# ftdi.net
KiCad netlist of a schematic drawn in EAGLE
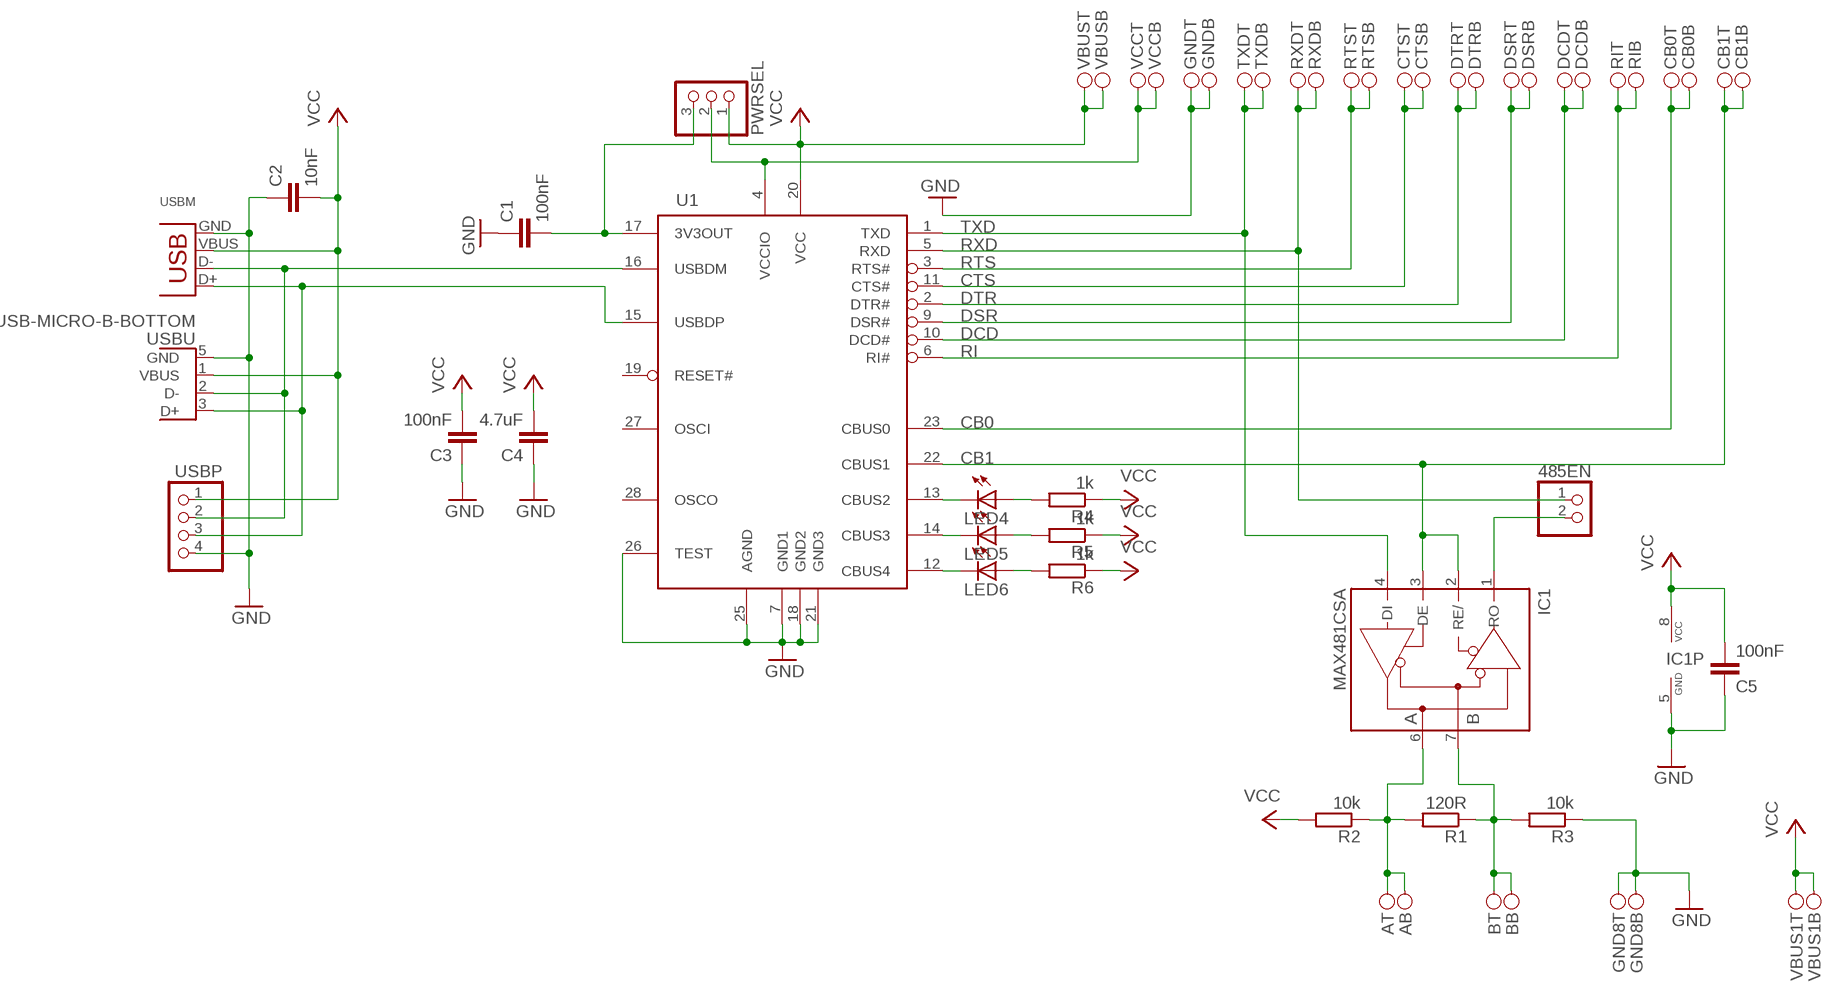
[diagram p0: schematic, sheet 1]

(export (version "E")
  (design (tool "Eeschema 10.0.6"))
  (components
    (comp (ref "485EN")
      (value "PINHD-1X2/90")
      (footprint "eagle-import:1X02_90")
      (libsource (lib "eagle-import") (part "PINHD-1X2/90"))
    )
    (comp (ref "A")
      (value "PINH2X01")
      (footprint "eagle-import:PINH2X01SMD")
      (libsource (lib "eagle-import") (part "PINH2X01"))
    )
    (comp (ref "B")
      (value "PINH2X01")
      (footprint "eagle-import:PINH2X01SMD")
      (libsource (lib "eagle-import") (part "PINH2X01"))
    )
    (comp (ref "C1")
      (value "100nF")
      (footprint "eagle-import:C0402")
      (libsource (lib "eagle-import") (part "C-EUC0402"))
    )
    (comp (ref "C2")
      (value "10nF")
      (footprint "eagle-import:C0603")
      (libsource (lib "eagle-import") (part "C-EUC0603"))
    )
    (comp (ref "C3")
      (value "100nF")
      (footprint "eagle-import:C0402")
      (libsource (lib "eagle-import") (part "C-EUC0402"))
    )
    (comp (ref "C4")
      (value "4.7uF")
      (footprint "eagle-import:C0805K")
      (libsource (lib "eagle-import") (part "C-EUC0805K"))
    )
    (comp (ref "C5")
      (value "100nF")
      (footprint "eagle-import:C0402")
      (libsource (lib "eagle-import") (part "C-EUC0402"))
    )
    (comp (ref "CB0")
      (value "PINH2X01")
      (footprint "eagle-import:PINH2X01SMD")
      (libsource (lib "eagle-import") (part "PINH2X01"))
    )
    (comp (ref "CB1")
      (value "PINH2X01")
      (footprint "eagle-import:PINH2X01SMD")
      (libsource (lib "eagle-import") (part "PINH2X01"))
    )
    (comp (ref "CTS")
      (value "PINH2X01")
      (footprint "eagle-import:PINH2X01SMD")
      (libsource (lib "eagle-import") (part "PINH2X01"))
    )
    (comp (ref "DCD")
      (value "PINH2X01")
      (footprint "eagle-import:PINH2X01SMD")
      (libsource (lib "eagle-import") (part "PINH2X01"))
    )
    (comp (ref "DSR")
      (value "PINH2X01")
      (footprint "eagle-import:PINH2X01SMD")
      (libsource (lib "eagle-import") (part "PINH2X01"))
    )
    (comp (ref "DTR")
      (value "PINH2X01")
      (footprint "eagle-import:PINH2X01SMD")
      (libsource (lib "eagle-import") (part "PINH2X01"))
    )
    (comp (ref "GND")
      (value "PINH2X01")
      (footprint "eagle-import:PINH2X01SMD")
      (libsource (lib "eagle-import") (part "PINH2X01"))
    )
    (comp (ref "GND8")
      (value "PINH2X01")
      (footprint "eagle-import:PINH2X01SMD")
      (libsource (lib "eagle-import") (part "PINH2X01"))
    )
    (comp (ref "IC1")
      (value "MAX481CSA")
      (footprint "eagle-import:SO08")
      (fields (field (name "MF") "MAXIM"))
      (libsource (lib "eagle-import") (part "MAX481CSA"))
    )
    (comp (ref "LED4")
      (value "LEDCHIPLED_0603")
      (footprint "eagle-import:CHIPLED_0603")
      (libsource (lib "eagle-import") (part "LEDCHIPLED_0603"))
    )
    (comp (ref "LED5")
      (value "LEDCHIPLED_0603")
      (footprint "eagle-import:CHIPLED_0603")
      (libsource (lib "eagle-import") (part "LEDCHIPLED_0603"))
    )
    (comp (ref "LED6")
      (value "LEDCHIPLED_0603")
      (footprint "eagle-import:CHIPLED_0603")
      (libsource (lib "eagle-import") (part "LEDCHIPLED_0603"))
    )
    (comp (ref "PWRSEL")
      (value "PINHD-1X3/90")
      (footprint "eagle-import:1X03_90")
      (libsource (lib "eagle-import") (part "PINHD-1X3/90"))
    )
    (comp (ref "R1")
      (value "120R")
      (footprint "eagle-import:R0603")
      (libsource (lib "eagle-import") (part "R-EU_R0603"))
    )
    (comp (ref "R2")
      (value "10k")
      (footprint "eagle-import:R0603")
      (libsource (lib "eagle-import") (part "R-EU_R0603"))
    )
    (comp (ref "R3")
      (value "10k")
      (footprint "eagle-import:R0603")
      (libsource (lib "eagle-import") (part "R-EU_R0603"))
    )
    (comp (ref "R4")
      (value "1k")
      (footprint "eagle-import:R0603")
      (libsource (lib "eagle-import") (part "R-EU_R0603"))
    )
    (comp (ref "R5")
      (value "1k")
      (footprint "eagle-import:R0603")
      (libsource (lib "eagle-import") (part "R-EU_R0603"))
    )
    (comp (ref "R6")
      (value "1k")
      (footprint "eagle-import:R0603")
      (libsource (lib "eagle-import") (part "R-EU_R0603"))
    )
    (comp (ref "RI")
      (value "PINH2X01")
      (footprint "eagle-import:PINH2X01SMD")
      (libsource (lib "eagle-import") (part "PINH2X01"))
    )
    (comp (ref "RTS")
      (value "PINH2X01")
      (footprint "eagle-import:PINH2X01SMD")
      (libsource (lib "eagle-import") (part "PINH2X01"))
    )
    (comp (ref "RXD")
      (value "PINH2X01")
      (footprint "eagle-import:PINH2X01SMD")
      (libsource (lib "eagle-import") (part "PINH2X01"))
    )
    (comp (ref "TXD")
      (value "PINH2X01")
      (footprint "eagle-import:PINH2X01SMD")
      (libsource (lib "eagle-import") (part "PINH2X01"))
    )
    (comp (ref "U1")
      (value "FT232RL")
      (footprint "eagle-import:SSOP28DB")
      (libsource (lib "eagle-import") (part "FT232RL"))
    )
    (comp (ref "USBM")
      (value "USB-MB-S")
      (footprint "eagle-import:USB-MB-S")
      (libsource (lib "eagle-import") (part "USB-MB-S"))
    )
    (comp (ref "USBP")
      (value "PINHD-1X4")
      (footprint "eagle-import:1X04")
      (libsource (lib "eagle-import") (part "PINHD-1X4"))
    )
    (comp (ref "USBU")
      (value "USB-MICRO-B-BOTTOM")
      (footprint "eagle-import:USB-MICRO-B-BOTTOM-MOLEX")
      (libsource (lib "eagle-import") (part "USB-MICRO-B-BOTTOM"))
    )
    (comp (ref "VBUS")
      (value "PINH2X01")
      (footprint "eagle-import:PINH2X01SMD")
      (libsource (lib "eagle-import") (part "PINH2X01"))
    )
    (comp (ref "VBUS1")
      (value "PINH2X01")
      (footprint "eagle-import:PINH2X01SMD")
      (libsource (lib "eagle-import") (part "PINH2X01"))
    )
    (comp (ref "VCC")
      (value "PINH2X01")
      (footprint "eagle-import:PINH2X01SMD")
      (libsource (lib "eagle-import") (part "PINH2X01"))
    )
  )
  (nets
    (net (code "1") (name "/CB0") (class "Default")
      (node (ref "CB0") (pin "1") (pinfunction "1_1") (pintype "passive"))
      (node (ref "CB0") (pin "2") (pinfunction "1_2") (pintype "passive"))
      (node (ref "U1") (pin "23") (pinfunction "CBUS0_23") (pintype "bidirectional"))
    )
    (net (code "2") (name "/CB1") (class "Default")
      (node (ref "CB1") (pin "1") (pinfunction "1_1") (pintype "passive"))
      (node (ref "CB1") (pin "2") (pinfunction "1_2") (pintype "passive"))
      (node (ref "IC1") (pin "2") (pinfunction "RE/_2") (pintype "input"))
      (node (ref "IC1") (pin "3") (pinfunction "DE_3") (pintype "input"))
      (node (ref "U1") (pin "22") (pinfunction "CBUS1_22") (pintype "bidirectional"))
    )
    (net (code "3") (name "/CTS") (class "Default")
      (node (ref "CTS") (pin "1") (pinfunction "1_1") (pintype "passive"))
      (node (ref "CTS") (pin "2") (pinfunction "1_2") (pintype "passive"))
      (node (ref "U1") (pin "11") (pinfunction "CTS#_11") (pintype "input"))
    )
    (net (code "4") (name "/DCD") (class "Default")
      (node (ref "DCD") (pin "1") (pinfunction "1_1") (pintype "passive"))
      (node (ref "DCD") (pin "2") (pinfunction "1_2") (pintype "passive"))
      (node (ref "U1") (pin "10") (pinfunction "DCD#_10") (pintype "input"))
    )
    (net (code "5") (name "/DSR") (class "Default")
      (node (ref "DSR") (pin "1") (pinfunction "1_1") (pintype "passive"))
      (node (ref "DSR") (pin "2") (pinfunction "1_2") (pintype "passive"))
      (node (ref "U1") (pin "9") (pinfunction "DSR#_9") (pintype "input"))
    )
    (net (code "6") (name "/DTR") (class "Default")
      (node (ref "DTR") (pin "1") (pinfunction "1_1") (pintype "passive"))
      (node (ref "DTR") (pin "2") (pinfunction "1_2") (pintype "passive"))
      (node (ref "U1") (pin "2") (pinfunction "DTR#_2") (pintype "output"))
    )
    (net (code "7") (name "/RI") (class "Default")
      (node (ref "RI") (pin "1") (pinfunction "1_1") (pintype "passive"))
      (node (ref "RI") (pin "2") (pinfunction "1_2") (pintype "passive"))
      (node (ref "U1") (pin "6") (pinfunction "RI#_6") (pintype "input"))
    )
    (net (code "8") (name "/RTS") (class "Default")
      (node (ref "RTS") (pin "1") (pinfunction "1_1") (pintype "passive"))
      (node (ref "RTS") (pin "2") (pinfunction "1_2") (pintype "passive"))
      (node (ref "U1") (pin "3") (pinfunction "RTS#_3") (pintype "output"))
    )
    (net (code "9") (name "/RXD") (class "Default")
      (node (ref "485EN") (pin "1") (pinfunction "1_1") (pintype "passive"))
      (node (ref "RXD") (pin "1") (pinfunction "1_1") (pintype "passive"))
      (node (ref "RXD") (pin "2") (pinfunction "1_2") (pintype "passive"))
      (node (ref "U1") (pin "5") (pinfunction "RXD_5") (pintype "input"))
    )
    (net (code "10") (name "/TXD") (class "Default")
      (node (ref "IC1") (pin "4") (pinfunction "DI_4") (pintype "input"))
      (node (ref "TXD") (pin "1") (pinfunction "1_1") (pintype "passive"))
      (node (ref "TXD") (pin "2") (pinfunction "1_2") (pintype "passive"))
      (node (ref "U1") (pin "1") (pinfunction "TXD_1") (pintype "output"))
    )
    (net (code "11") (name "GND") (class "Default")
      (node (ref "C1") (pin "1") (pinfunction "1_1") (pintype "passive"))
      (node (ref "C2") (pin "1") (pinfunction "1_1") (pintype "passive"))
      (node (ref "C3") (pin "1") (pinfunction "1_1") (pintype "passive"))
      (node (ref "C4") (pin "1") (pinfunction "1_1") (pintype "passive"))
      (node (ref "C5") (pin "1") (pinfunction "1_1") (pintype "passive"))
      (node (ref "GND") (pin "1") (pinfunction "1_1") (pintype "passive"))
      (node (ref "GND") (pin "2") (pinfunction "1_2") (pintype "passive"))
      (node (ref "GND8") (pin "1") (pinfunction "1_1") (pintype "passive"))
      (node (ref "GND8") (pin "2") (pinfunction "1_2") (pintype "passive"))
      (node (ref "IC1") (pin "5") (pinfunction "GND_5") (pintype "power_in"))
      (node (ref "R3") (pin "1") (pinfunction "1_1") (pintype "passive"))
      (node (ref "U1") (pin "18") (pinfunction "GND2_18") (pintype "power_in"))
      (node (ref "U1") (pin "21") (pinfunction "GND3_21") (pintype "power_in"))
      (node (ref "U1") (pin "25") (pinfunction "AGND_25") (pintype "power_in"))
      (node (ref "U1") (pin "26") (pinfunction "TEST_26") (pintype "input"))
      (node (ref "U1") (pin "7") (pinfunction "GND1_7") (pintype "power_in"))
      (node (ref "USBM") (pin "GND") (pinfunction "GND_GND") (pintype "bidirectional"))
      (node (ref "USBP") (pin "4") (pinfunction "4_4") (pintype "passive"))
      (node (ref "USBU") (pin "5") (pinfunction "GND_5") (pintype "passive"))
    )
    (net (code "12") (name "Net-(AA-1)") (class "Default")
      (node (ref "A") (pin "1") (pinfunction "1_1") (pintype "passive"))
      (node (ref "A") (pin "2") (pinfunction "1_2") (pintype "passive"))
      (node (ref "IC1") (pin "6") (pinfunction "A_6") (pintype "passive"))
      (node (ref "R1") (pin "2") (pinfunction "2_2") (pintype "passive"))
      (node (ref "R2") (pin "1") (pinfunction "1_1") (pintype "passive"))
    )
    (net (code "13") (name "Net-(BA-1)") (class "Default")
      (node (ref "B") (pin "1") (pinfunction "1_1") (pintype "passive"))
      (node (ref "B") (pin "2") (pinfunction "1_2") (pintype "passive"))
      (node (ref "IC1") (pin "7") (pinfunction "B_7") (pintype "passive"))
      (node (ref "R1") (pin "1") (pinfunction "1_1") (pintype "passive"))
      (node (ref "R3") (pin "2") (pinfunction "2_2") (pintype "passive"))
    )
    (net (code "14") (name "Net-(IC1A-RO)") (class "Default")
      (node (ref "485EN") (pin "2") (pinfunction "2_2") (pintype "passive"))
      (node (ref "IC1") (pin "1") (pinfunction "RO_1") (pintype "output"))
    )
    (net (code "15") (name "Net-(LED4-PadA)") (class "Default")
      (node (ref "LED4") (pin "A") (pinfunction "A_A") (pintype "passive"))
      (node (ref "R4") (pin "2") (pinfunction "2_2") (pintype "passive"))
    )
    (net (code "16") (name "Net-(LED5-PadA)") (class "Default")
      (node (ref "LED5") (pin "A") (pinfunction "A_A") (pintype "passive"))
      (node (ref "R5") (pin "2") (pinfunction "2_2") (pintype "passive"))
    )
    (net (code "17") (name "Net-(LED6-PadA)") (class "Default")
      (node (ref "LED6") (pin "A") (pinfunction "A_A") (pintype "passive"))
      (node (ref "R6") (pin "2") (pinfunction "2_2") (pintype "passive"))
    )
    (net (code "18") (name "Net-(U1-3V3OUT)") (class "Default")
      (node (ref "C1") (pin "2") (pinfunction "2_2") (pintype "passive"))
      (node (ref "PWRSEL") (pin "3") (pinfunction "3_3") (pintype "passive"))
      (node (ref "U1") (pin "17") (pinfunction "3V3OUT_17") (pintype "output"))
    )
    (net (code "19") (name "Net-(U1-CBUS2)") (class "Default")
      (node (ref "LED4") (pin "C") (pinfunction "C_C") (pintype "passive"))
      (node (ref "U1") (pin "13") (pinfunction "CBUS2_13") (pintype "bidirectional"))
    )
    (net (code "20") (name "Net-(U1-CBUS3)") (class "Default")
      (node (ref "LED5") (pin "C") (pinfunction "C_C") (pintype "passive"))
      (node (ref "U1") (pin "14") (pinfunction "CBUS3_14") (pintype "bidirectional"))
    )
    (net (code "21") (name "Net-(U1-CBUS4)") (class "Default")
      (node (ref "LED6") (pin "C") (pinfunction "C_C") (pintype "passive"))
      (node (ref "U1") (pin "12") (pinfunction "CBUS4_12") (pintype "bidirectional"))
    )
    (net (code "22") (name "Net-(U1-USBDM)") (class "Default")
      (node (ref "U1") (pin "16") (pinfunction "USBDM_16") (pintype "bidirectional"))
      (node (ref "USBM") (pin "D-") (pinfunction "D-_D-") (pintype "bidirectional"))
      (node (ref "USBP") (pin "2") (pinfunction "2_2") (pintype "passive"))
      (node (ref "USBU") (pin "2") (pinfunction "D-_2") (pintype "bidirectional"))
    )
    (net (code "23") (name "Net-(U1-USBDP)") (class "Default")
      (node (ref "U1") (pin "15") (pinfunction "USBDP_15") (pintype "bidirectional"))
      (node (ref "USBM") (pin "D+") (pinfunction "D+_D+") (pintype "bidirectional"))
      (node (ref "USBP") (pin "3") (pinfunction "3_3") (pintype "passive"))
      (node (ref "USBU") (pin "3") (pinfunction "D+_3") (pintype "bidirectional"))
    )
    (net (code "24") (name "Net-(U1-VCCIO)") (class "Default")
      (node (ref "PWRSEL") (pin "2") (pinfunction "2_2") (pintype "passive"))
      (node (ref "U1") (pin "4") (pinfunction "VCCIO_4") (pintype "power_in"))
      (node (ref "VCC") (pin "1") (pinfunction "1_1") (pintype "passive"))
      (node (ref "VCC") (pin "2") (pinfunction "1_2") (pintype "passive"))
    )
    (net (code "25") (name "VCC") (class "Default")
      (node (ref "C2") (pin "2") (pinfunction "2_2") (pintype "passive"))
      (node (ref "C3") (pin "2") (pinfunction "2_2") (pintype "passive"))
      (node (ref "C4") (pin "2") (pinfunction "2_2") (pintype "passive"))
      (node (ref "C5") (pin "2") (pinfunction "2_2") (pintype "passive"))
      (node (ref "IC1") (pin "8") (pinfunction "VCC_8") (pintype "power_in"))
      (node (ref "PWRSEL") (pin "1") (pinfunction "1_1") (pintype "passive"))
      (node (ref "R2") (pin "2") (pinfunction "2_2") (pintype "passive"))
      (node (ref "R4") (pin "1") (pinfunction "1_1") (pintype "passive"))
      (node (ref "R5") (pin "1") (pinfunction "1_1") (pintype "passive"))
      (node (ref "R6") (pin "1") (pinfunction "1_1") (pintype "passive"))
      (node (ref "U1") (pin "20") (pinfunction "VCC_20") (pintype "power_in"))
      (node (ref "USBM") (pin "VBUS") (pinfunction "VBUS_VBUS") (pintype "bidirectional"))
      (node (ref "USBP") (pin "1") (pinfunction "1_1") (pintype "passive"))
      (node (ref "USBU") (pin "1") (pinfunction "VBUS_1") (pintype "passive"))
      (node (ref "VBUS") (pin "1") (pinfunction "1_1") (pintype "passive"))
      (node (ref "VBUS") (pin "2") (pinfunction "1_2") (pintype "passive"))
      (node (ref "VBUS1") (pin "1") (pinfunction "1_1") (pintype "passive"))
      (node (ref "VBUS1") (pin "2") (pinfunction "1_2") (pintype "passive"))
    )
    (net (code "26") (name "unconnected-(U1-OSCI-Pad27)") (class "Default")
      (node (ref "U1") (pin "27") (pinfunction "OSCI_27") (pintype "input"))
    )
    (net (code "27") (name "unconnected-(U1-OSCO-Pad28)") (class "Default")
      (node (ref "U1") (pin "28") (pinfunction "OSCO_28") (pintype "output"))
    )
    (net (code "28") (name "unconnected-(U1-RESET#-Pad19)") (class "Default")
      (node (ref "U1") (pin "19") (pinfunction "RESET#_19") (pintype "input"))
    )
  )
)
